# CH348L.net
KiCad netlist of a schematic drawn in EAGLE
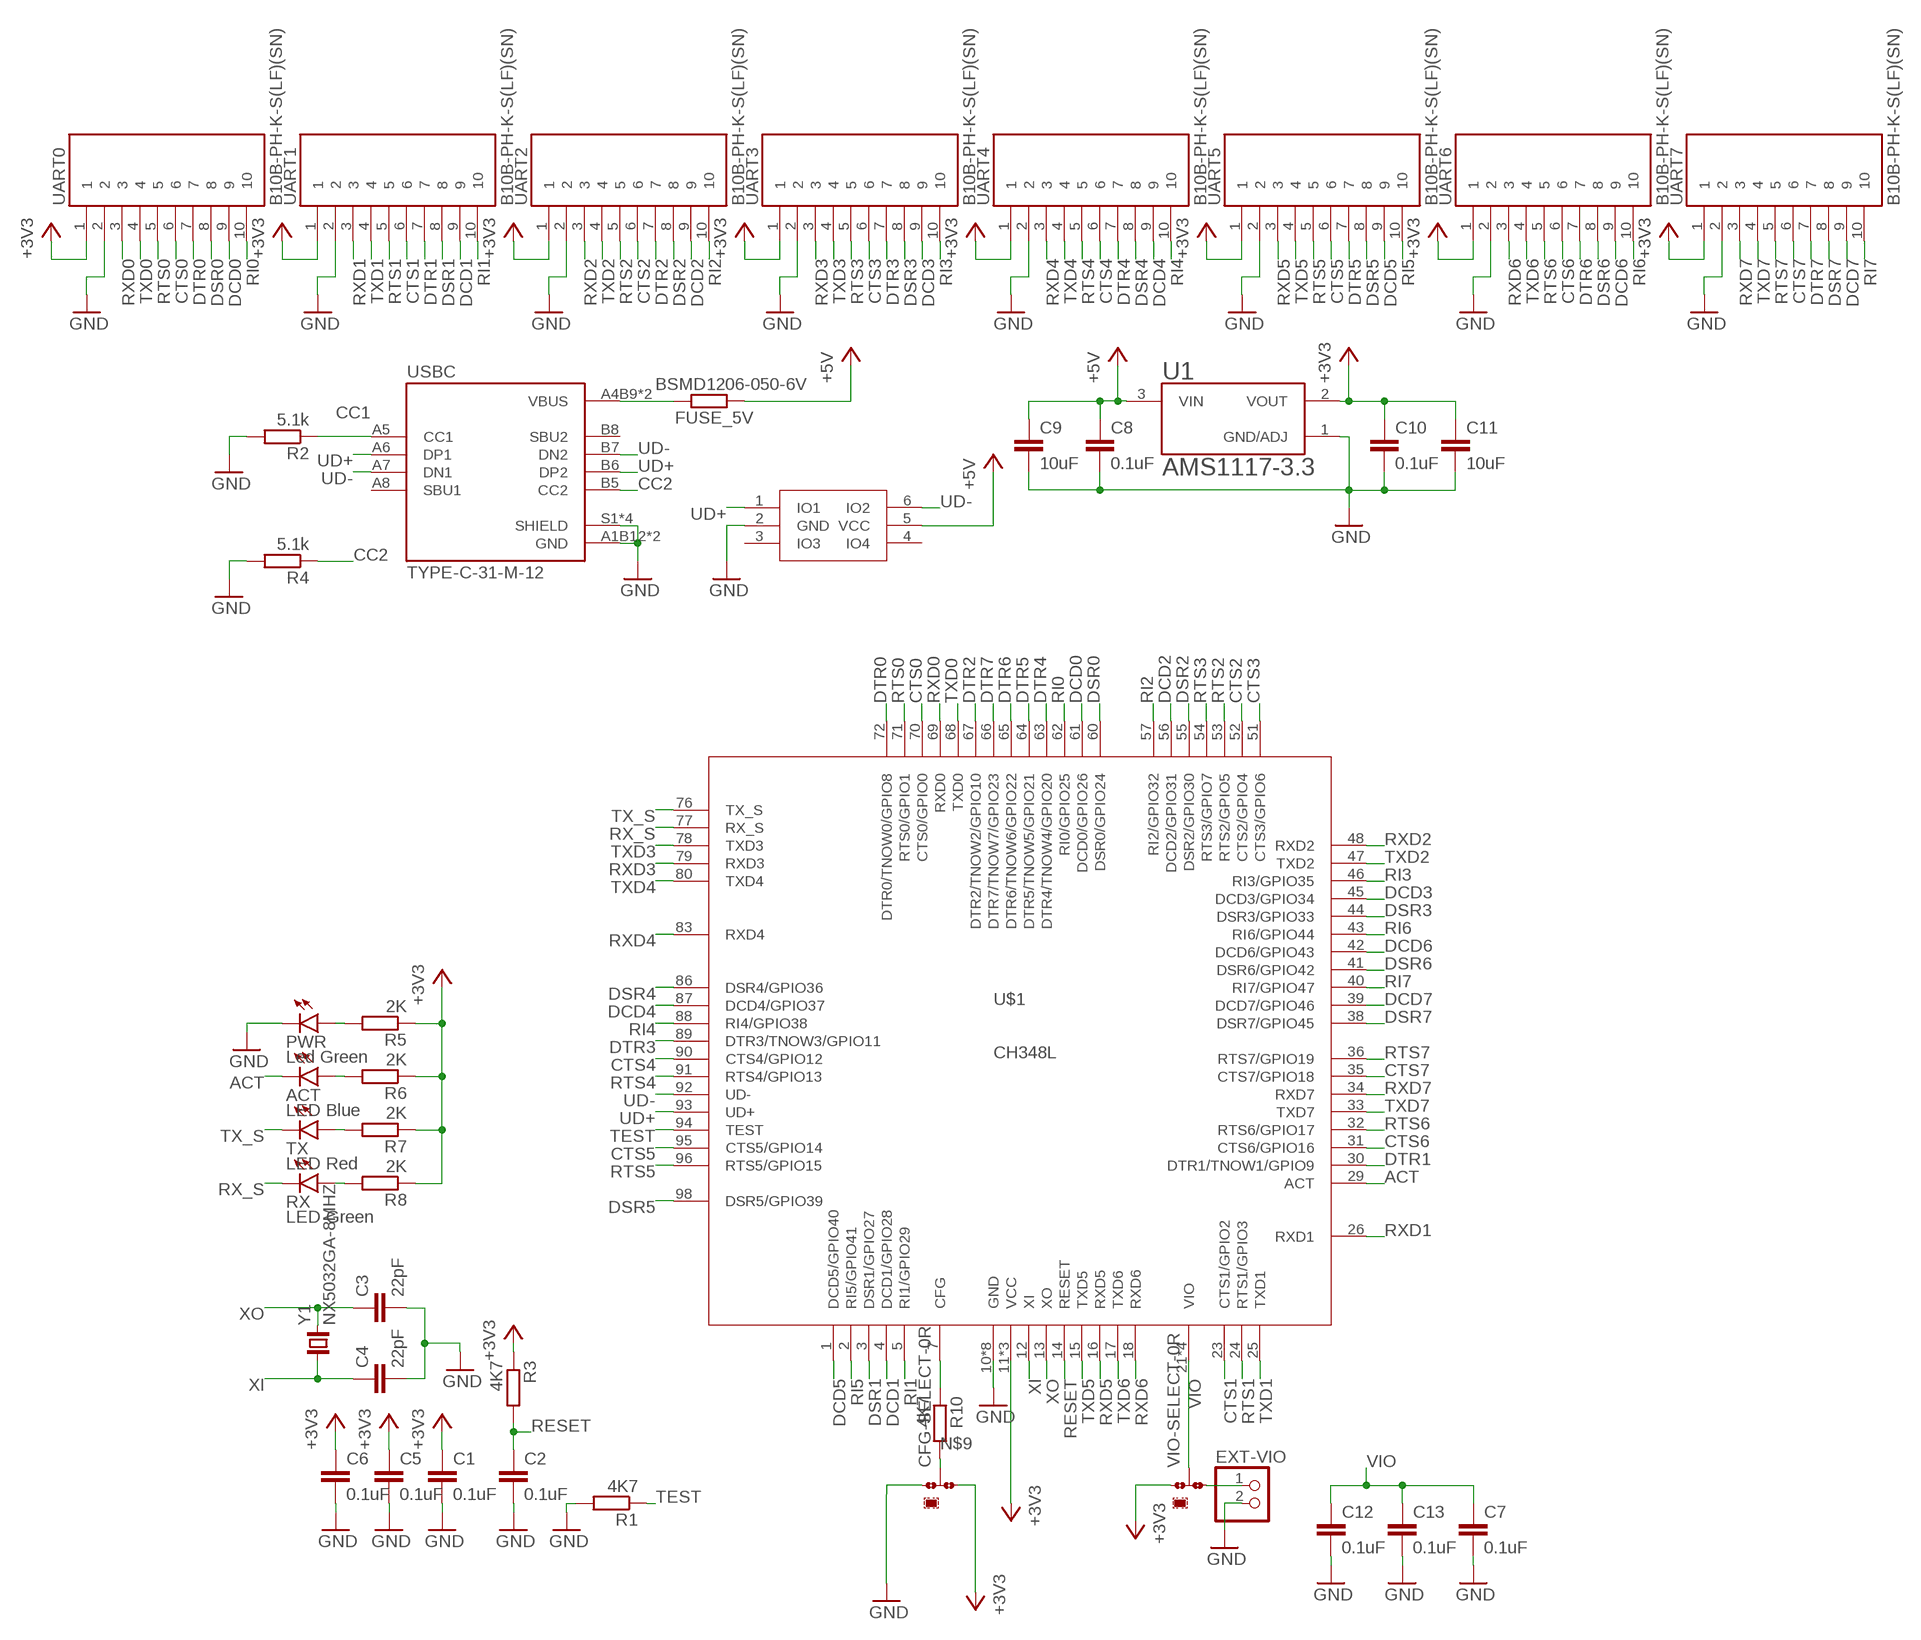
[diagram p0: schematic, sheet 1]

(export (version "E")
  (design (tool "Eeschema 10.0.6"))
  (components
    (comp (ref "ACT")
      (value "LED Blue")
      (footprint "eagle-import:CHIP-LED0603")
      (libsource (lib "eagle-import") (part "LEDCHIP-LED0603"))
    )
    (comp (ref "C1")
      (value "0.1uF")
      (footprint "eagle-import:C0603")
      (libsource (lib "eagle-import") (part "C-EUC0603"))
    )
    (comp (ref "C2")
      (value "0.1uF")
      (footprint "eagle-import:C0603")
      (libsource (lib "eagle-import") (part "C-EUC0603"))
    )
    (comp (ref "C3")
      (value "22pF")
      (footprint "eagle-import:C0603")
      (libsource (lib "eagle-import") (part "C-EUC0603"))
    )
    (comp (ref "C4")
      (value "22pF")
      (footprint "eagle-import:C0603")
      (libsource (lib "eagle-import") (part "C-EUC0603"))
    )
    (comp (ref "C5")
      (value "0.1uF")
      (footprint "eagle-import:C0603")
      (libsource (lib "eagle-import") (part "C-EUC0603"))
    )
    (comp (ref "C6")
      (value "0.1uF")
      (footprint "eagle-import:C0603")
      (libsource (lib "eagle-import") (part "C-EUC0603"))
    )
    (comp (ref "C7")
      (value "0.1uF")
      (footprint "eagle-import:C0603")
      (libsource (lib "eagle-import") (part "C-EUC0603"))
    )
    (comp (ref "C8")
      (value "0.1uF")
      (footprint "eagle-import:C0603")
      (libsource (lib "eagle-import") (part "C-EUC0603"))
    )
    (comp (ref "C9")
      (value "10uF")
      (footprint "eagle-import:C0805")
      (libsource (lib "eagle-import") (part "C-EUC0805"))
    )
    (comp (ref "C10")
      (value "0.1uF")
      (footprint "eagle-import:C0603")
      (libsource (lib "eagle-import") (part "C-EUC0603"))
    )
    (comp (ref "C11")
      (value "10uF")
      (footprint "eagle-import:C0805")
      (libsource (lib "eagle-import") (part "C-EUC0805"))
    )
    (comp (ref "C12")
      (value "0.1uF")
      (footprint "eagle-import:C0603")
      (libsource (lib "eagle-import") (part "C-EUC0603"))
    )
    (comp (ref "C13")
      (value "0.1uF")
      (footprint "eagle-import:C0603")
      (libsource (lib "eagle-import") (part "C-EUC0603"))
    )
    (comp (ref "CFG-SELECT")
      (value "0R-JUMPA")
      (footprint "eagle-import:A0R-JMP")
      (libsource (lib "eagle-import") (part "0R-JUMPA"))
    )
    (comp (ref "EXT-VIO")
      (value "PINHD-1X2")
      (footprint "eagle-import:1X02")
      (libsource (lib "eagle-import") (part "PINHD-1X2"))
    )
    (comp (ref "FUSE_5V")
      (value "BSMD1206-050-6V")
      (footprint "eagle-import:R1206")
      (libsource (lib "eagle-import") (part "R-EU_R1206"))
    )
    (comp (ref "PWR")
      (value "Led Green")
      (footprint "eagle-import:CHIP-LED0603")
      (libsource (lib "eagle-import") (part "LEDCHIP-LED0603"))
    )
    (comp (ref "R1")
      (value "4K7")
      (footprint "eagle-import:R0603")
      (libsource (lib "eagle-import") (part "R-EU_R0603"))
    )
    (comp (ref "R2")
      (value "5.1k")
      (footprint "eagle-import:R0603")
      (libsource (lib "eagle-import") (part "R-EU_R0603"))
    )
    (comp (ref "R3")
      (value "4K7")
      (footprint "eagle-import:R0603")
      (libsource (lib "eagle-import") (part "R-EU_R0603"))
    )
    (comp (ref "R4")
      (value "5.1k")
      (footprint "eagle-import:R0603")
      (libsource (lib "eagle-import") (part "R-EU_R0603"))
    )
    (comp (ref "R5")
      (value "2K")
      (footprint "eagle-import:R0603")
      (libsource (lib "eagle-import") (part "R-EU_R0603"))
    )
    (comp (ref "R6")
      (value "2K")
      (footprint "eagle-import:R0603")
      (libsource (lib "eagle-import") (part "R-EU_R0603"))
    )
    (comp (ref "R7")
      (value "2K")
      (footprint "eagle-import:R0603")
      (libsource (lib "eagle-import") (part "R-EU_R0603"))
    )
    (comp (ref "R8")
      (value "2K")
      (footprint "eagle-import:R0603")
      (libsource (lib "eagle-import") (part "R-EU_R0603"))
    )
    (comp (ref "R10")
      (value "4K7")
      (footprint "eagle-import:R0603")
      (libsource (lib "eagle-import") (part "R-EU_R0603"))
    )
    (comp (ref "RX")
      (value "LED Green")
      (footprint "eagle-import:CHIP-LED0603")
      (libsource (lib "eagle-import") (part "LEDCHIP-LED0603"))
    )
    (comp (ref "TX")
      (value "LED Red")
      (footprint "eagle-import:CHIP-LED0603")
      (libsource (lib "eagle-import") (part "LEDCHIP-LED0603"))
    )
    (comp (ref "U$1")
      (value "CH348L")
      (footprint "eagle-import:LQFP100_14X14")
      (libsource (lib "eagle-import") (part "CH348L"))
    )
    (comp (ref "U1")
      (value "AMS1117-3.3")
      (footprint "eagle-import:SOT229P700X180-4N")
      (fields (field (name "MF") "Advanced Monolithic Systems"))
      (libsource (lib "eagle-import") (part "AMS1117-3.3"))
    )
    (comp (ref "U5")
      (value "ESDU5V0H4")
      (footprint "eagle-import:SOT-23-6")
      (libsource (lib "eagle-import") (part "ESDU5V0H4"))
    )
    (comp (ref "UART0")
      (value "B10B-PH-K-S(LF)(SN)")
      (footprint "eagle-import:JST_S10B-PH-K-S(LF)(SN)")
      (fields (field (name "MF") "JST Sales") (field (name "MP") "S6B-PH-K-S(LF)(SN)"))
      (libsource (lib "eagle-import") (part "S10B-PH-K-S(LF)(SN)"))
    )
    (comp (ref "UART1")
      (value "B10B-PH-K-S(LF)(SN)")
      (footprint "eagle-import:JST_S10B-PH-K-S(LF)(SN)")
      (fields (field (name "MF") "JST Sales") (field (name "MP") "S6B-PH-K-S(LF)(SN)"))
      (libsource (lib "eagle-import") (part "S10B-PH-K-S(LF)(SN)"))
    )
    (comp (ref "UART2")
      (value "B10B-PH-K-S(LF)(SN)")
      (footprint "eagle-import:JST_S10B-PH-K-S(LF)(SN)")
      (fields (field (name "MF") "JST Sales") (field (name "MP") "S6B-PH-K-S(LF)(SN)"))
      (libsource (lib "eagle-import") (part "S10B-PH-K-S(LF)(SN)"))
    )
    (comp (ref "UART3")
      (value "B10B-PH-K-S(LF)(SN)")
      (footprint "eagle-import:JST_S10B-PH-K-S(LF)(SN)")
      (fields (field (name "MF") "JST Sales") (field (name "MP") "S6B-PH-K-S(LF)(SN)"))
      (libsource (lib "eagle-import") (part "S10B-PH-K-S(LF)(SN)"))
    )
    (comp (ref "UART4")
      (value "B10B-PH-K-S(LF)(SN)")
      (footprint "eagle-import:JST_S10B-PH-K-S(LF)(SN)")
      (fields (field (name "MF") "JST Sales") (field (name "MP") "S6B-PH-K-S(LF)(SN)"))
      (libsource (lib "eagle-import") (part "S10B-PH-K-S(LF)(SN)"))
    )
    (comp (ref "UART5")
      (value "B10B-PH-K-S(LF)(SN)")
      (footprint "eagle-import:JST_S10B-PH-K-S(LF)(SN)")
      (fields (field (name "MF") "JST Sales") (field (name "MP") "S6B-PH-K-S(LF)(SN)"))
      (libsource (lib "eagle-import") (part "S10B-PH-K-S(LF)(SN)"))
    )
    (comp (ref "UART6")
      (value "B10B-PH-K-S(LF)(SN)")
      (footprint "eagle-import:JST_S10B-PH-K-S(LF)(SN)")
      (fields (field (name "MF") "JST Sales") (field (name "MP") "S6B-PH-K-S(LF)(SN)"))
      (libsource (lib "eagle-import") (part "S10B-PH-K-S(LF)(SN)"))
    )
    (comp (ref "UART7")
      (value "B10B-PH-K-S(LF)(SN)")
      (footprint "eagle-import:JST_S10B-PH-K-S(LF)(SN)")
      (fields (field (name "MF") "JST Sales") (field (name "MP") "S6B-PH-K-S(LF)(SN)"))
      (libsource (lib "eagle-import") (part "S10B-PH-K-S(LF)(SN)"))
    )
    (comp (ref "USBC")
      (value "TYPE-C-31-M-12")
      (footprint "eagle-import:HRO_TYPE-C-31-M-12")
      (fields (field (name "MF") "HRO Electronics Co., Ltd."))
      (libsource (lib "eagle-import") (part "TYPE-C-31-M-12"))
    )
    (comp (ref "VIO-SELECT")
      (value "0R-JUMPA")
      (footprint "eagle-import:A0R-JMP")
      (libsource (lib "eagle-import") (part "0R-JUMPA"))
    )
    (comp (ref "Y1")
      (value "NX5032GA-8MHZ")
      (footprint "eagle-import:2-SMD-5X3")
      (fields (field (name "MF") "NDK America,") (field (name "MP") "NX5032GA"))
      (libsource (lib "eagle-import") (part "NX5032GA"))
    )
  )
  (nets
    (net (code "1") (name "+3V3") (class "Default")
      (node (ref "C1") (pin "1") (pinfunction "1_1") (pintype "passive"))
      (node (ref "C10") (pin "1") (pinfunction "1_1") (pintype "passive"))
      (node (ref "C11") (pin "1") (pinfunction "1_1") (pintype "passive"))
      (node (ref "C5") (pin "1") (pinfunction "1_1") (pintype "passive"))
      (node (ref "C6") (pin "1") (pinfunction "1_1") (pintype "passive"))
      (node (ref "CFG-SELECT") (pin "3") (pinfunction "3_3") (pintype "passive"))
      (node (ref "R3") (pin "1") (pinfunction "1_1") (pintype "passive"))
      (node (ref "R5") (pin "1") (pinfunction "1_1") (pintype "passive"))
      (node (ref "R6") (pin "1") (pinfunction "1_1") (pintype "passive"))
      (node (ref "R7") (pin "1") (pinfunction "1_1") (pintype "passive"))
      (node (ref "R8") (pin "1") (pinfunction "1_1") (pintype "passive"))
      (node (ref "U$1") (pin "11") (pinfunction "VCC_11") (pintype "bidirectional"))
      (node (ref "U$1") (pin "28") (pinfunction "VCC_28") (pintype "bidirectional"))
      (node (ref "U$1") (pin "75") (pinfunction "VCC_75") (pintype "bidirectional"))
      (node (ref "U1") (pin "2") (pinfunction "VOUT_2") (pintype "output"))
      (node (ref "UART0") (pin "1") (pinfunction "1_1") (pintype "passive"))
      (node (ref "UART1") (pin "1") (pinfunction "1_1") (pintype "passive"))
      (node (ref "UART2") (pin "1") (pinfunction "1_1") (pintype "passive"))
      (node (ref "UART3") (pin "1") (pinfunction "1_1") (pintype "passive"))
      (node (ref "UART4") (pin "1") (pinfunction "1_1") (pintype "passive"))
      (node (ref "UART5") (pin "1") (pinfunction "1_1") (pintype "passive"))
      (node (ref "UART6") (pin "1") (pinfunction "1_1") (pintype "passive"))
      (node (ref "UART7") (pin "1") (pinfunction "1_1") (pintype "passive"))
      (node (ref "VIO-SELECT") (pin "1") (pinfunction "1_1") (pintype "passive"))
    )
    (net (code "2") (name "+5V") (class "Default")
      (node (ref "C8") (pin "1") (pinfunction "1_1") (pintype "passive"))
      (node (ref "C9") (pin "1") (pinfunction "1_1") (pintype "passive"))
      (node (ref "FUSE_5V") (pin "1") (pinfunction "1_1") (pintype "passive"))
      (node (ref "U1") (pin "3") (pinfunction "VIN_3") (pintype "input"))
      (node (ref "U5") (pin "5") (pinfunction "VCC_5") (pintype "bidirectional"))
    )
    (net (code "3") (name "/ACT") (class "Default")
      (node (ref "ACT") (pin "C") (pinfunction "C_C") (pintype "passive"))
      (node (ref "U$1") (pin "29") (pinfunction "ACT_29") (pintype "bidirectional"))
    )
    (net (code "4") (name "/CC1") (class "Default")
      (node (ref "R2") (pin "1") (pinfunction "1_1") (pintype "passive"))
      (node (ref "USBC") (pin "A5") (pinfunction "CC1_A5") (pintype "bidirectional"))
    )
    (net (code "5") (name "/CC2") (class "Default")
      (node (ref "R4") (pin "1") (pinfunction "1_1") (pintype "passive"))
      (node (ref "USBC") (pin "B5") (pinfunction "CC2_B5") (pintype "bidirectional"))
    )
    (net (code "6") (name "/CTS0") (class "Default")
      (node (ref "U$1") (pin "70") (pinfunction "CTS0/GPIO0_70") (pintype "bidirectional"))
      (node (ref "UART0") (pin "6") (pinfunction "6_6") (pintype "passive"))
    )
    (net (code "7") (name "/CTS1") (class "Default")
      (node (ref "U$1") (pin "23") (pinfunction "CTS1/GPIO2_23") (pintype "bidirectional"))
      (node (ref "UART1") (pin "6") (pinfunction "6_6") (pintype "passive"))
    )
    (net (code "8") (name "/CTS2") (class "Default")
      (node (ref "U$1") (pin "52") (pinfunction "CTS2/GPIO4_52") (pintype "bidirectional"))
      (node (ref "UART2") (pin "6") (pinfunction "6_6") (pintype "passive"))
    )
    (net (code "9") (name "/CTS3") (class "Default")
      (node (ref "U$1") (pin "51") (pinfunction "CTS3/GPIO6_51") (pintype "bidirectional"))
      (node (ref "UART3") (pin "6") (pinfunction "6_6") (pintype "passive"))
    )
    (net (code "10") (name "/CTS4") (class "Default")
      (node (ref "U$1") (pin "90") (pinfunction "CTS4/GPIO12_90") (pintype "bidirectional"))
      (node (ref "UART4") (pin "6") (pinfunction "6_6") (pintype "passive"))
    )
    (net (code "11") (name "/CTS5") (class "Default")
      (node (ref "U$1") (pin "95") (pinfunction "CTS5/GPIO14_95") (pintype "bidirectional"))
      (node (ref "UART5") (pin "6") (pinfunction "6_6") (pintype "passive"))
    )
    (net (code "12") (name "/CTS6") (class "Default")
      (node (ref "U$1") (pin "31") (pinfunction "CTS6/GPIO16_31") (pintype "bidirectional"))
      (node (ref "UART6") (pin "6") (pinfunction "6_6") (pintype "passive"))
    )
    (net (code "13") (name "/CTS7") (class "Default")
      (node (ref "U$1") (pin "35") (pinfunction "CTS7/GPIO18_35") (pintype "bidirectional"))
      (node (ref "UART7") (pin "6") (pinfunction "6_6") (pintype "passive"))
    )
    (net (code "14") (name "/DCD0") (class "Default")
      (node (ref "U$1") (pin "61") (pinfunction "DCD0/GPIO26_61") (pintype "bidirectional"))
      (node (ref "UART0") (pin "9") (pinfunction "9_9") (pintype "passive"))
    )
    (net (code "15") (name "/DCD1") (class "Default")
      (node (ref "U$1") (pin "4") (pinfunction "DCD1/GPIO28_4") (pintype "bidirectional"))
      (node (ref "UART1") (pin "9") (pinfunction "9_9") (pintype "passive"))
    )
    (net (code "16") (name "/DCD2") (class "Default")
      (node (ref "U$1") (pin "56") (pinfunction "DCD2/GPIO31_56") (pintype "bidirectional"))
      (node (ref "UART2") (pin "9") (pinfunction "9_9") (pintype "passive"))
    )
    (net (code "17") (name "/DCD3") (class "Default")
      (node (ref "U$1") (pin "45") (pinfunction "DCD3/GPIO34_45") (pintype "bidirectional"))
      (node (ref "UART3") (pin "9") (pinfunction "9_9") (pintype "passive"))
    )
    (net (code "18") (name "/DCD4") (class "Default")
      (node (ref "U$1") (pin "87") (pinfunction "DCD4/GPIO37_87") (pintype "bidirectional"))
      (node (ref "UART4") (pin "9") (pinfunction "9_9") (pintype "passive"))
    )
    (net (code "19") (name "/DCD5") (class "Default")
      (node (ref "U$1") (pin "1") (pinfunction "DCD5/GPIO40_1") (pintype "bidirectional"))
      (node (ref "UART5") (pin "9") (pinfunction "9_9") (pintype "passive"))
    )
    (net (code "20") (name "/DCD6") (class "Default")
      (node (ref "U$1") (pin "42") (pinfunction "DCD6/GPIO43_42") (pintype "bidirectional"))
      (node (ref "UART6") (pin "9") (pinfunction "9_9") (pintype "passive"))
    )
    (net (code "21") (name "/DCD7") (class "Default")
      (node (ref "U$1") (pin "39") (pinfunction "DCD7/GPIO46_39") (pintype "bidirectional"))
      (node (ref "UART7") (pin "9") (pinfunction "9_9") (pintype "passive"))
    )
    (net (code "22") (name "/DSR0") (class "Default")
      (node (ref "U$1") (pin "60") (pinfunction "DSR0/GPIO24_60") (pintype "bidirectional"))
      (node (ref "UART0") (pin "8") (pinfunction "8_8") (pintype "passive"))
    )
    (net (code "23") (name "/DSR1") (class "Default")
      (node (ref "U$1") (pin "3") (pinfunction "DSR1/GPIO27_3") (pintype "bidirectional"))
      (node (ref "UART1") (pin "8") (pinfunction "8_8") (pintype "passive"))
    )
    (net (code "24") (name "/DSR2") (class "Default")
      (node (ref "U$1") (pin "55") (pinfunction "DSR2/GPIO30_55") (pintype "bidirectional"))
      (node (ref "UART2") (pin "8") (pinfunction "8_8") (pintype "passive"))
    )
    (net (code "25") (name "/DSR3") (class "Default")
      (node (ref "U$1") (pin "44") (pinfunction "DSR3/GPIO33_44") (pintype "bidirectional"))
      (node (ref "UART3") (pin "8") (pinfunction "8_8") (pintype "passive"))
    )
    (net (code "26") (name "/DSR4") (class "Default")
      (node (ref "U$1") (pin "86") (pinfunction "DSR4/GPIO36_86") (pintype "bidirectional"))
      (node (ref "UART4") (pin "8") (pinfunction "8_8") (pintype "passive"))
    )
    (net (code "27") (name "/DSR5") (class "Default")
      (node (ref "U$1") (pin "98") (pinfunction "DSR5/GPIO39_98") (pintype "bidirectional"))
      (node (ref "UART5") (pin "8") (pinfunction "8_8") (pintype "passive"))
    )
    (net (code "28") (name "/DSR6") (class "Default")
      (node (ref "U$1") (pin "41") (pinfunction "DSR6/GPIO42_41") (pintype "bidirectional"))
      (node (ref "UART6") (pin "8") (pinfunction "8_8") (pintype "passive"))
    )
    (net (code "29") (name "/DSR7") (class "Default")
      (node (ref "U$1") (pin "38") (pinfunction "DSR7/GPIO45_38") (pintype "bidirectional"))
      (node (ref "UART7") (pin "8") (pinfunction "8_8") (pintype "passive"))
    )
    (net (code "30") (name "/DTR0") (class "Default")
      (node (ref "U$1") (pin "72") (pinfunction "DTR0/TNOW0/GPIO8_72") (pintype "bidirectional"))
      (node (ref "UART0") (pin "7") (pinfunction "7_7") (pintype "passive"))
    )
    (net (code "31") (name "/DTR1") (class "Default")
      (node (ref "U$1") (pin "30") (pinfunction "DTR1/TNOW1/GPIO9_30") (pintype "bidirectional"))
      (node (ref "UART1") (pin "7") (pinfunction "7_7") (pintype "passive"))
    )
    (net (code "32") (name "/DTR2") (class "Default")
      (node (ref "U$1") (pin "67") (pinfunction "DTR2/TNOW2/GPIO10_67") (pintype "bidirectional"))
      (node (ref "UART2") (pin "7") (pinfunction "7_7") (pintype "passive"))
    )
    (net (code "33") (name "/DTR3") (class "Default")
      (node (ref "U$1") (pin "89") (pinfunction "DTR3/TNOW3/GPIO11_89") (pintype "bidirectional"))
      (node (ref "UART3") (pin "7") (pinfunction "7_7") (pintype "passive"))
    )
    (net (code "34") (name "/DTR4") (class "Default")
      (node (ref "U$1") (pin "63") (pinfunction "DTR4/TNOW4/GPIO20_63") (pintype "bidirectional"))
      (node (ref "UART4") (pin "7") (pinfunction "7_7") (pintype "passive"))
    )
    (net (code "35") (name "/DTR5") (class "Default")
      (node (ref "U$1") (pin "64") (pinfunction "DTR5/TNOW5/GPIO21_64") (pintype "bidirectional"))
      (node (ref "UART5") (pin "7") (pinfunction "7_7") (pintype "passive"))
    )
    (net (code "36") (name "/DTR6") (class "Default")
      (node (ref "U$1") (pin "65") (pinfunction "DTR6/TNOW6/GPIO22_65") (pintype "bidirectional"))
      (node (ref "UART6") (pin "7") (pinfunction "7_7") (pintype "passive"))
    )
    (net (code "37") (name "/DTR7") (class "Default")
      (node (ref "U$1") (pin "66") (pinfunction "DTR7/TNOW7/GPIO23_66") (pintype "bidirectional"))
      (node (ref "UART7") (pin "7") (pinfunction "7_7") (pintype "passive"))
    )
    (net (code "38") (name "/N$9") (class "Default")
      (node (ref "CFG-SELECT") (pin "2") (pinfunction "2_2") (pintype "passive"))
      (node (ref "R10") (pin "2") (pinfunction "2_2") (pintype "passive"))
    )
    (net (code "39") (name "/RESET") (class "Default")
      (node (ref "C2") (pin "1") (pinfunction "1_1") (pintype "passive"))
      (node (ref "R3") (pin "2") (pinfunction "2_2") (pintype "passive"))
      (node (ref "U$1") (pin "14") (pinfunction "RESET_14") (pintype "bidirectional"))
    )
    (net (code "40") (name "/RI0") (class "Default")
      (node (ref "U$1") (pin "62") (pinfunction "RI0/GPIO25_62") (pintype "bidirectional"))
      (node (ref "UART0") (pin "10") (pinfunction "10_10") (pintype "passive"))
    )
    (net (code "41") (name "/RI1") (class "Default")
      (node (ref "U$1") (pin "5") (pinfunction "RI1/GPIO29_5") (pintype "bidirectional"))
      (node (ref "UART1") (pin "10") (pinfunction "10_10") (pintype "passive"))
    )
    (net (code "42") (name "/RI2") (class "Default")
      (node (ref "U$1") (pin "57") (pinfunction "RI2/GPIO32_57") (pintype "bidirectional"))
      (node (ref "UART2") (pin "10") (pinfunction "10_10") (pintype "passive"))
    )
    (net (code "43") (name "/RI3") (class "Default")
      (node (ref "U$1") (pin "46") (pinfunction "RI3/GPIO35_46") (pintype "bidirectional"))
      (node (ref "UART3") (pin "10") (pinfunction "10_10") (pintype "passive"))
    )
    (net (code "44") (name "/RI4") (class "Default")
      (node (ref "U$1") (pin "88") (pinfunction "RI4/GPIO38_88") (pintype "bidirectional"))
      (node (ref "UART4") (pin "10") (pinfunction "10_10") (pintype "passive"))
    )
    (net (code "45") (name "/RI5") (class "Default")
      (node (ref "U$1") (pin "2") (pinfunction "RI5/GPIO41_2") (pintype "bidirectional"))
      (node (ref "UART5") (pin "10") (pinfunction "10_10") (pintype "passive"))
    )
    (net (code "46") (name "/RI6") (class "Default")
      (node (ref "U$1") (pin "43") (pinfunction "RI6/GPIO44_43") (pintype "bidirectional"))
      (node (ref "UART6") (pin "10") (pinfunction "10_10") (pintype "passive"))
    )
    (net (code "47") (name "/RI7") (class "Default")
      (node (ref "U$1") (pin "40") (pinfunction "RI7/GPIO47_40") (pintype "bidirectional"))
      (node (ref "UART7") (pin "10") (pinfunction "10_10") (pintype "passive"))
    )
    (net (code "48") (name "/RTS0") (class "Default")
      (node (ref "U$1") (pin "71") (pinfunction "RTS0/GPIO1_71") (pintype "bidirectional"))
      (node (ref "UART0") (pin "5") (pinfunction "5_5") (pintype "passive"))
    )
    (net (code "49") (name "/RTS1") (class "Default")
      (node (ref "U$1") (pin "24") (pinfunction "RTS1/GPIO3_24") (pintype "bidirectional"))
      (node (ref "UART1") (pin "5") (pinfunction "5_5") (pintype "passive"))
    )
    (net (code "50") (name "/RTS2") (class "Default")
      (node (ref "U$1") (pin "53") (pinfunction "RTS2/GPIO5_53") (pintype "bidirectional"))
      (node (ref "UART2") (pin "5") (pinfunction "5_5") (pintype "passive"))
    )
    (net (code "51") (name "/RTS3") (class "Default")
      (node (ref "U$1") (pin "54") (pinfunction "RTS3/GPIO7_54") (pintype "bidirectional"))
      (node (ref "UART3") (pin "5") (pinfunction "5_5") (pintype "passive"))
    )
    (net (code "52") (name "/RTS4") (class "Default")
      (node (ref "U$1") (pin "91") (pinfunction "RTS4/GPIO13_91") (pintype "bidirectional"))
      (node (ref "UART4") (pin "5") (pinfunction "5_5") (pintype "passive"))
    )
    (net (code "53") (name "/RTS5") (class "Default")
      (node (ref "U$1") (pin "96") (pinfunction "RTS5/GPIO15_96") (pintype "bidirectional"))
      (node (ref "UART5") (pin "5") (pinfunction "5_5") (pintype "passive"))
    )
    (net (code "54") (name "/RTS6") (class "Default")
      (node (ref "U$1") (pin "32") (pinfunction "RTS6/GPIO17_32") (pintype "bidirectional"))
      (node (ref "UART6") (pin "5") (pinfunction "5_5") (pintype "passive"))
    )
    (net (code "55") (name "/RTS7") (class "Default")
      (node (ref "U$1") (pin "36") (pinfunction "RTS7/GPIO19_36") (pintype "bidirectional"))
      (node (ref "UART7") (pin "5") (pinfunction "5_5") (pintype "passive"))
    )
    (net (code "56") (name "/RXD0") (class "Default")
      (node (ref "U$1") (pin "69") (pinfunction "RXD0_69") (pintype "bidirectional"))
      (node (ref "UART0") (pin "3") (pinfunction "3_3") (pintype "passive"))
    )
    (net (code "57") (name "/RXD1") (class "Default")
      (node (ref "U$1") (pin "26") (pinfunction "RXD1_26") (pintype "bidirectional"))
      (node (ref "UART1") (pin "3") (pinfunction "3_3") (pintype "passive"))
    )
    (net (code "58") (name "/RXD2") (class "Default")
      (node (ref "U$1") (pin "48") (pinfunction "RXD2_48") (pintype "bidirectional"))
      (node (ref "UART2") (pin "3") (pinfunction "3_3") (pintype "passive"))
    )
    (net (code "59") (name "/RXD3") (class "Default")
      (node (ref "U$1") (pin "79") (pinfunction "RXD3_79") (pintype "bidirectional"))
      (node (ref "UART3") (pin "3") (pinfunction "3_3") (pintype "passive"))
    )
    (net (code "60") (name "/RXD4") (class "Default")
      (node (ref "U$1") (pin "83") (pinfunction "RXD4_83") (pintype "bidirectional"))
      (node (ref "UART4") (pin "3") (pinfunction "3_3") (pintype "passive"))
    )
    (net (code "61") (name "/RXD5") (class "Default")
      (node (ref "U$1") (pin "16") (pinfunction "RXD5_16") (pintype "bidirectional"))
      (node (ref "UART5") (pin "3") (pinfunction "3_3") (pintype "passive"))
    )
    (net (code "62") (name "/RXD6") (class "Default")
      (node (ref "U$1") (pin "18") (pinfunction "RXD6_18") (pintype "bidirectional"))
      (node (ref "UART6") (pin "3") (pinfunction "3_3") (pintype "passive"))
    )
    (net (code "63") (name "/RXD7") (class "Default")
      (node (ref "U$1") (pin "34") (pinfunction "RXD7_34") (pintype "bidirectional"))
      (node (ref "UART7") (pin "3") (pinfunction "3_3") (pintype "passive"))
    )
    (net (code "64") (name "/RX_S") (class "Default")
      (node (ref "RX") (pin "C") (pinfunction "C_C") (pintype "passive"))
      (node (ref "U$1") (pin "77") (pinfunction "RX_S_77") (pintype "bidirectional"))
    )
    (net (code "65") (name "/TEST") (class "Default")
      (node (ref "R1") (pin "1") (pinfunction "1_1") (pintype "passive"))
      (node (ref "U$1") (pin "94") (pinfunction "TEST_94") (pintype "bidirectional"))
    )
    (net (code "66") (name "/TXD0") (class "Default")
      (node (ref "U$1") (pin "68") (pinfunction "TXD0_68") (pintype "bidirectional"))
      (node (ref "UART0") (pin "4") (pinfunction "4_4") (pintype "passive"))
    )
    (net (code "67") (name "/TXD1") (class "Default")
      (node (ref "U$1") (pin "25") (pinfunction "TXD1_25") (pintype "bidirectional"))
      (node (ref "UART1") (pin "4") (pinfunction "4_4") (pintype "passive"))
    )
    (net (code "68") (name "/TXD2") (class "Default")
      (node (ref "U$1") (pin "47") (pinfunction "TXD2_47") (pintype "bidirectional"))
      (node (ref "UART2") (pin "4") (pinfunction "4_4") (pintype "passive"))
    )
    (net (code "69") (name "/TXD3") (class "Default")
      (node (ref "U$1") (pin "78") (pinfunction "TXD3_78") (pintype "bidirectional"))
      (node (ref "UART3") (pin "4") (pinfunction "4_4") (pintype "passive"))
    )
    (net (code "70") (name "/TXD4") (class "Default")
      (node (ref "U$1") (pin "80") (pinfunction "TXD4_80") (pintype "bidirectional"))
      (node (ref "UART4") (pin "4") (pinfunction "4_4") (pintype "passive"))
    )
    (net (code "71") (name "/TXD5") (class "Default")
      (node (ref "U$1") (pin "15") (pinfunction "TXD5_15") (pintype "bidirectional"))
      (node (ref "UART5") (pin "4") (pinfunction "4_4") (pintype "passive"))
    )
    (net (code "72") (name "/TXD6") (class "Default")
      (node (ref "U$1") (pin "17") (pinfunction "TXD6_17") (pintype "bidirectional"))
      (node (ref "UART6") (pin "4") (pinfunction "4_4") (pintype "passive"))
    )
    (net (code "73") (name "/TXD7") (class "Default")
      (node (ref "U$1") (pin "33") (pinfunction "TXD7_33") (pintype "bidirectional"))
      (node (ref "UART7") (pin "4") (pinfunction "4_4") (pintype "passive"))
    )
    (net (code "74") (name "/TX_S") (class "Default")
      (node (ref "TX") (pin "C") (pinfunction "C_C") (pintype "passive"))
      (node (ref "U$1") (pin "76") (pinfunction "TX_S_76") (pintype "bidirectional"))
    )
    (net (code "75") (name "/UD+") (class "Default")
      (node (ref "U$1") (pin "93") (pinfunction "UD+_93") (pintype "bidirectional"))
      (node (ref "U5") (pin "1") (pinfunction "IO1_1") (pintype "bidirectional"))
      (node (ref "USBC") (pin "A6") (pinfunction "DP1_A6") (pintype "bidirectional"))
      (node (ref "USBC") (pin "B6") (pinfunction "DP2_B6") (pintype "bidirectional"))
    )
    (net (code "76") (name "/UD-") (class "Default")
      (node (ref "U$1") (pin "92") (pinfunction "UD-_92") (pintype "bidirectional"))
      (node (ref "U5") (pin "6") (pinfunction "IO2_6") (pintype "bidirectional"))
      (node (ref "USBC") (pin "A7") (pinfunction "DN1_A7") (pintype "bidirectional"))
      (node (ref "USBC") (pin "B7") (pinfunction "DN2_B7") (pintype "bidirectional"))
    )
    (net (code "77") (name "/VIO") (class "Default")
      (node (ref "C12") (pin "1") (pinfunction "1_1") (pintype "passive"))
      (node (ref "C13") (pin "1") (pinfunction "1_1") (pintype "passive"))
      (node (ref "C7") (pin "1") (pinfunction "1_1") (pintype "passive"))
      (node (ref "U$1") (pin "100") (pinfunction "VIO_100") (pintype "bidirectional"))
      (node (ref "U$1") (pin "21") (pinfunction "VIO_21") (pintype "bidirectional"))
      (node (ref "U$1") (pin "22") (pinfunction "VIO_22") (pintype "bidirectional"))
      (node (ref "U$1") (pin "50") (pinfunction "VIO_50") (pintype "bidirectional"))
      (node (ref "VIO-SELECT") (pin "2") (pinfunction "2_2") (pintype "passive"))
    )
    (net (code "78") (name "/XI") (class "Default")
      (node (ref "C4") (pin "1") (pinfunction "1_1") (pintype "passive"))
      (node (ref "U$1") (pin "12") (pinfunction "XI_12") (pintype "bidirectional"))
      (node (ref "Y1") (pin "1") (pinfunction "1_1") (pintype "passive"))
    )
    (net (code "79") (name "/XO") (class "Default")
      (node (ref "C3") (pin "1") (pinfunction "1_1") (pintype "passive"))
      (node (ref "U$1") (pin "13") (pinfunction "XO_13") (pintype "bidirectional"))
      (node (ref "Y1") (pin "2") (pinfunction "2_2") (pintype "passive"))
    )
    (net (code "80") (name "GND") (class "Default")
      (node (ref "C1") (pin "2") (pinfunction "2_2") (pintype "passive"))
      (node (ref "C10") (pin "2") (pinfunction "2_2") (pintype "passive"))
      (node (ref "C11") (pin "2") (pinfunction "2_2") (pintype "passive"))
      (node (ref "C12") (pin "2") (pinfunction "2_2") (pintype "passive"))
      (node (ref "C13") (pin "2") (pinfunction "2_2") (pintype "passive"))
      (node (ref "C2") (pin "2") (pinfunction "2_2") (pintype "passive"))
      (node (ref "C3") (pin "2") (pinfunction "2_2") (pintype "passive"))
      (node (ref "C4") (pin "2") (pinfunction "2_2") (pintype "passive"))
      (node (ref "C5") (pin "2") (pinfunction "2_2") (pintype "passive"))
      (node (ref "C6") (pin "2") (pinfunction "2_2") (pintype "passive"))
      (node (ref "C7") (pin "2") (pinfunction "2_2") (pintype "passive"))
      (node (ref "C8") (pin "2") (pinfunction "2_2") (pintype "passive"))
      (node (ref "C9") (pin "2") (pinfunction "2_2") (pintype "passive"))
      (node (ref "CFG-SELECT") (pin "1") (pinfunction "1_1") (pintype "passive"))
      (node (ref "EXT-VIO") (pin "2") (pinfunction "2_2") (pintype "passive"))
      (node (ref "PWR") (pin "C") (pinfunction "C_C") (pintype "passive"))
      (node (ref "R1") (pin "2") (pinfunction "2_2") (pintype "passive"))
      (node (ref "R2") (pin "2") (pinfunction "2_2") (pintype "passive"))
      (node (ref "R4") (pin "2") (pinfunction "2_2") (pintype "passive"))
      (node (ref "U$1") (pin "10") (pinfunction "GND_10") (pintype "bidirectional"))
      (node (ref "U$1") (pin "19") (pinfunction "GND_19") (pintype "bidirectional"))
      (node (ref "U$1") (pin "20") (pinfunction "GND_20") (pintype "bidirectional"))
      (node (ref "U$1") (pin "27") (pinfunction "GND_27") (pintype "bidirectional"))
      (node (ref "U$1") (pin "37") (pinfunction "GND_37") (pintype "bidirectional"))
      (node (ref "U$1") (pin "49") (pinfunction "GND_49") (pintype "bidirectional"))
      (node (ref "U$1") (pin "74") (pinfunction "GND_74") (pintype "bidirectional"))
      (node (ref "U$1") (pin "99") (pinfunction "GND_99") (pintype "bidirectional"))
      (node (ref "U1") (pin "1") (pinfunction "GND/ADJ_1") (pintype "power_in"))
      (node (ref "U5") (pin "2") (pinfunction "GND_2") (pintype "bidirectional"))
      (node (ref "UART0") (pin "2") (pinfunction "2_2") (pintype "passive"))
      (node (ref "UART1") (pin "2") (pinfunction "2_2") (pintype "passive"))
      (node (ref "UART2") (pin "2") (pinfunction "2_2") (pintype "passive"))
      (node (ref "UART3") (pin "2") (pinfunction "2_2") (pintype "passive"))
      (node (ref "UART4") (pin "2") (pinfunction "2_2") (pintype "passive"))
      (node (ref "UART5") (pin "2") (pinfunction "2_2") (pintype "passive"))
      (node (ref "UART6") (pin "2") (pinfunction "2_2") (pintype "passive"))
      (node (ref "UART7") (pin "2") (pinfunction "2_2") (pintype "passive"))
      (node (ref "USBC") (pin "A1B12") (pinfunction "GND_A1B12") (pintype "power_in"))
      (node (ref "USBC") (pin "B1A12") (pinfunction "GND_B1A12") (pintype "power_in"))
      (node (ref "USBC") (pin "S1") (pinfunction "SHIELD_S1") (pintype "passive"))
      (node (ref "USBC") (pin "S2") (pinfunction "SHIELD_S2") (pintype "passive"))
      (node (ref "USBC") (pin "S3") (pinfunction "SHIELD_S3") (pintype "passive"))
      (node (ref "USBC") (pin "S4") (pinfunction "SHIELD_S4") (pintype "passive"))
    )
    (net (code "81") (name "Net-(ACT-PadA)") (class "Default")
      (node (ref "ACT") (pin "A") (pinfunction "A_A") (pintype "passive"))
      (node (ref "R6") (pin "2") (pinfunction "2_2") (pintype "passive"))
    )
    (net (code "82") (name "Net-(EXT-VIO-Pad1)") (class "Default")
      (node (ref "EXT-VIO") (pin "1") (pinfunction "1_1") (pintype "passive"))
      (node (ref "VIO-SELECT") (pin "3") (pinfunction "3_3") (pintype "passive"))
    )
    (net (code "83") (name "Net-(FUSE_5V-Pad2)") (class "Default")
      (node (ref "FUSE_5V") (pin "2") (pinfunction "2_2") (pintype "passive"))
      (node (ref "USBC") (pin "A4B9") (pinfunction "VBUS_A4B9") (pintype "power_in"))
      (node (ref "USBC") (pin "B4A9") (pinfunction "VBUS_B4A9") (pintype "power_in"))
    )
    (net (code "84") (name "Net-(PWR-PadA)") (class "Default")
      (node (ref "PWR") (pin "A") (pinfunction "A_A") (pintype "passive"))
      (node (ref "R5") (pin "2") (pinfunction "2_2") (pintype "passive"))
    )
    (net (code "85") (name "Net-(R7-Pad2)") (class "Default")
      (node (ref "R7") (pin "2") (pinfunction "2_2") (pintype "passive"))
      (node (ref "TX") (pin "A") (pinfunction "A_A") (pintype "passive"))
    )
    (net (code "86") (name "Net-(R8-Pad2)") (class "Default")
      (node (ref "R8") (pin "2") (pinfunction "2_2") (pintype "passive"))
      (node (ref "RX") (pin "A") (pinfunction "A_A") (pintype "passive"))
    )
    (net (code "87") (name "Net-(U$1-CFG)") (class "Default")
      (node (ref "R10") (pin "1") (pinfunction "1_1") (pintype "passive"))
      (node (ref "U$1") (pin "7") (pinfunction "CFG_7") (pintype "bidirectional"))
    )
    (net (code "88") (name "unconnected-(U5-IO3-Pad3)") (class "Default")
      (node (ref "U5") (pin "3") (pinfunction "IO3_3") (pintype "bidirectional"))
    )
    (net (code "89") (name "unconnected-(U5-IO4-Pad4)") (class "Default")
      (node (ref "U5") (pin "4") (pinfunction "IO4_4") (pintype "bidirectional"))
    )
    (net (code "90") (name "unconnected-(USBC-SBU1-PadA8)") (class "Default")
      (node (ref "USBC") (pin "A8") (pinfunction "SBU1_A8") (pintype "bidirectional"))
    )
    (net (code "91") (name "unconnected-(USBC-SBU2-PadB8)") (class "Default")
      (node (ref "USBC") (pin "B8") (pinfunction "SBU2_B8") (pintype "bidirectional"))
    )
  )
)
